# STM32G431CBU6.net
KiCad netlist of a schematic drawn in Altium Designer
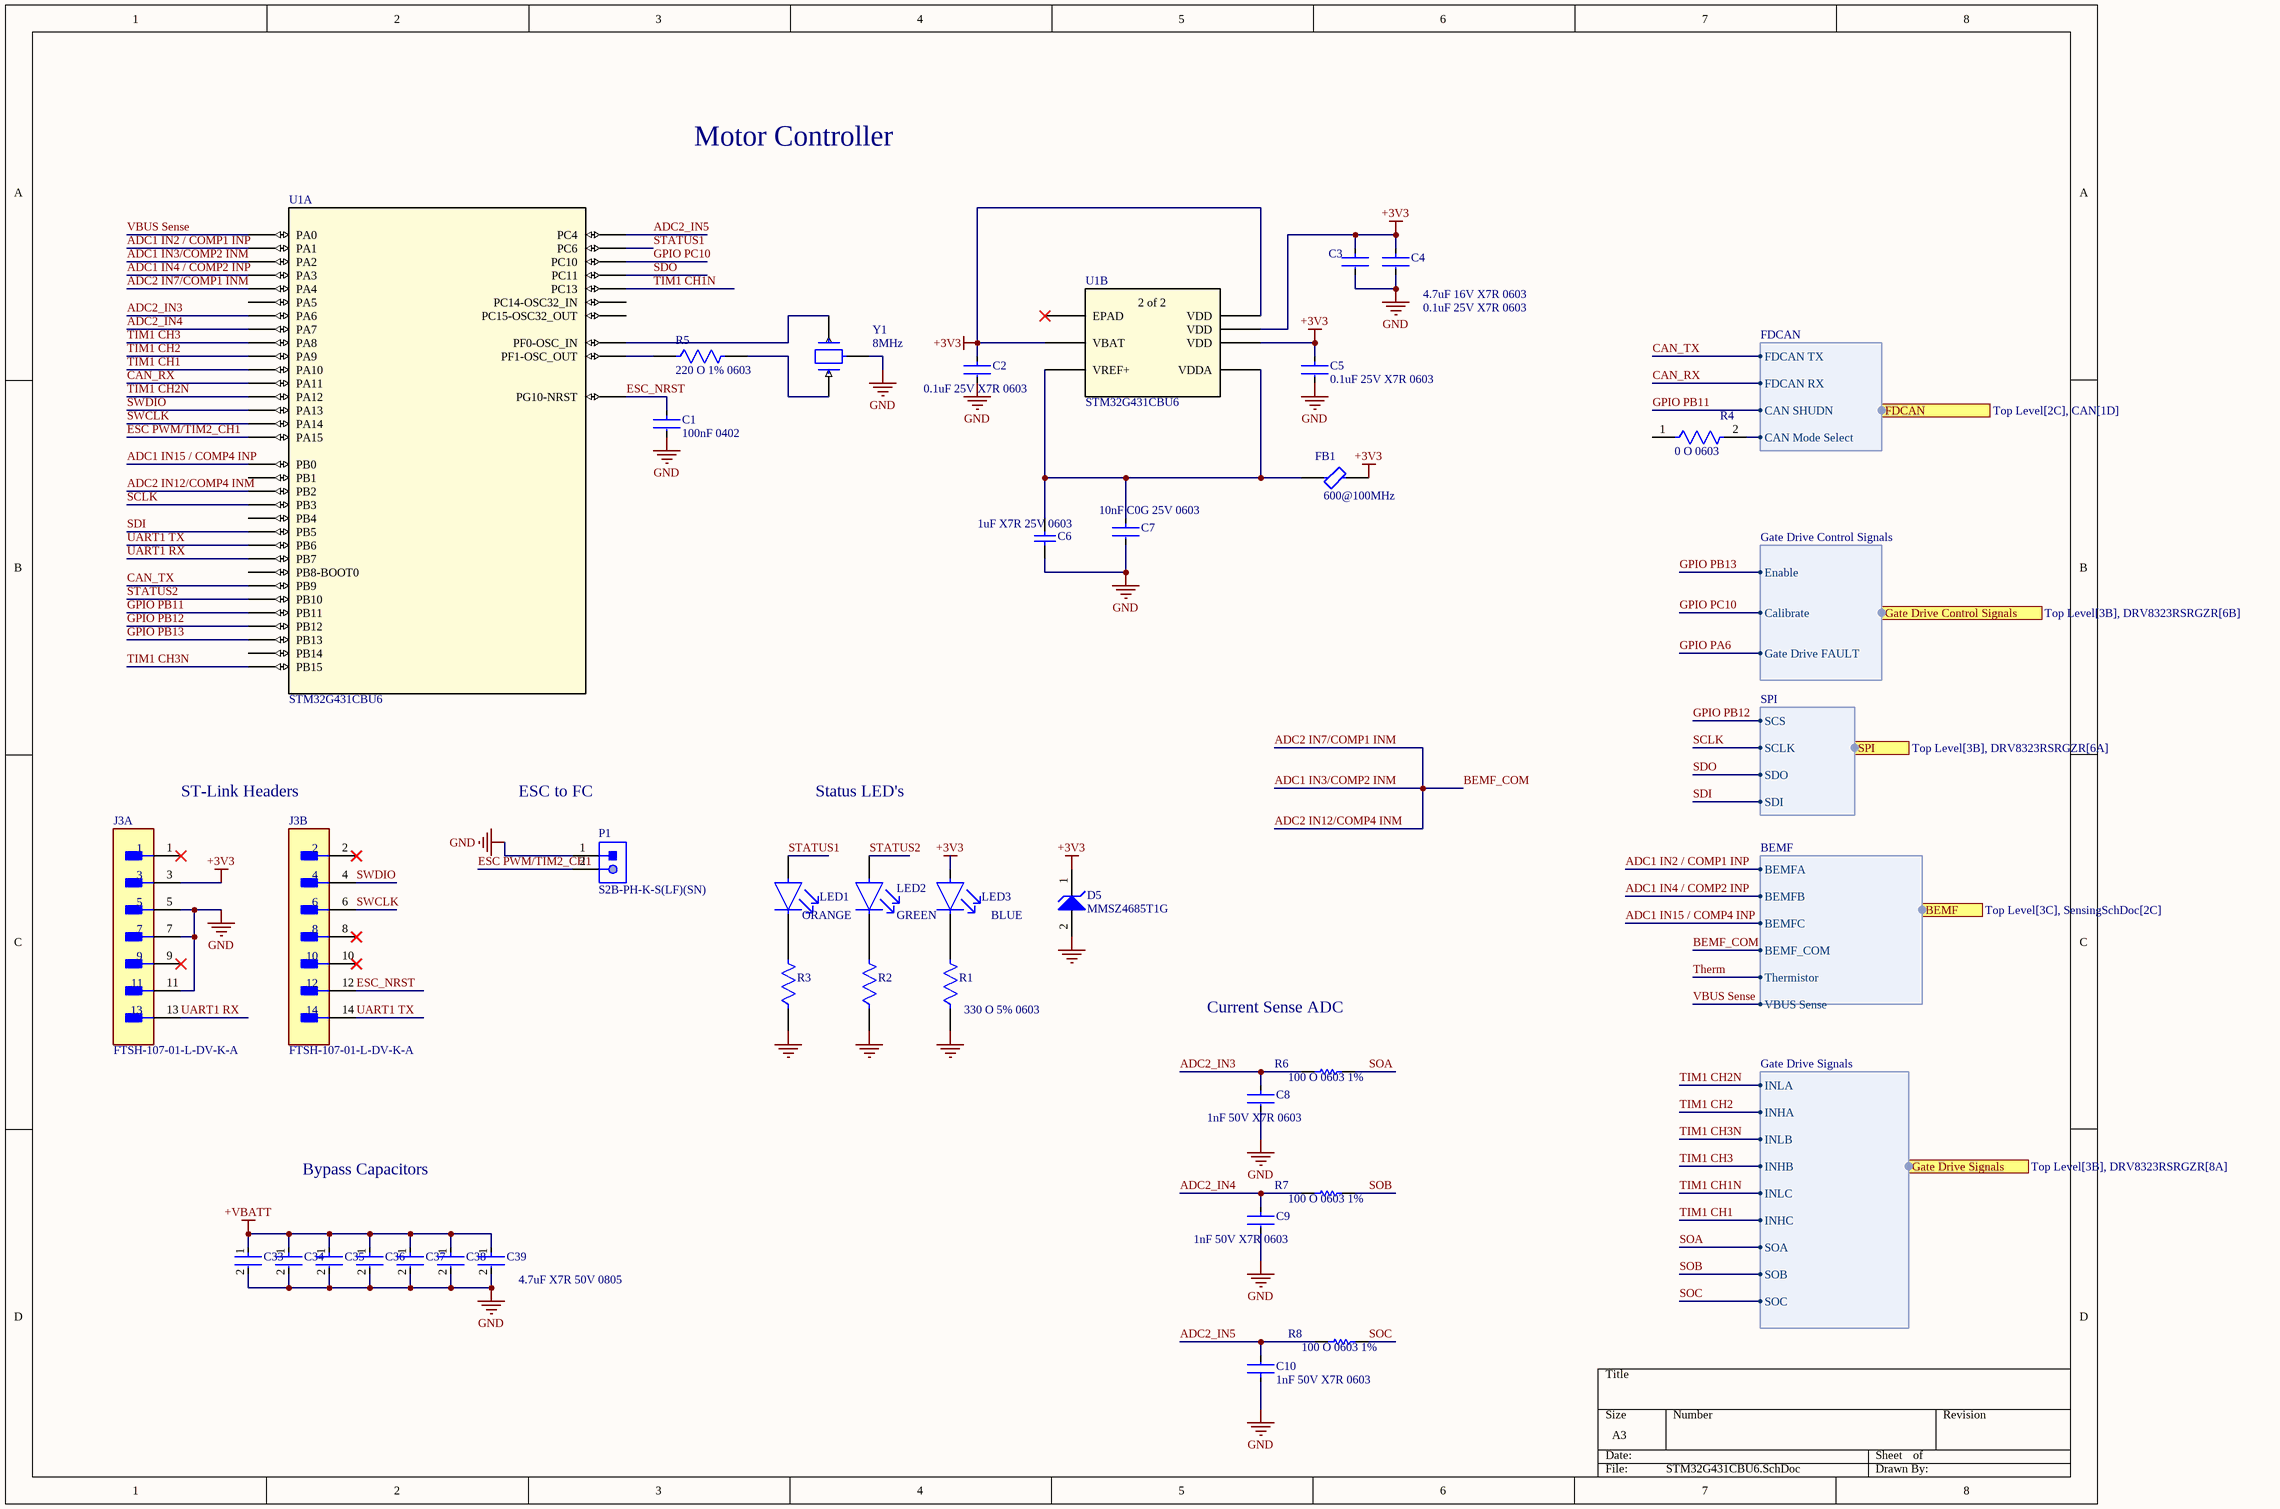
[diagram p0: STM32G431CBU6.SchDoc]

(export (version "E")
  (design (tool "Eeschema 10.0.6"))
  (components
    (comp (ref "C1")
      (value "100nF 0402")
      (footprint "FP-GRM155-0_05-MFG")
      (description "Chip Multilayer Ceramic Capacitors for General Purpose, 0402, 0.10uF, X7R, 15%, 20%, 25V")
      (libsource (lib "Altium Content Vault") (part "02cd4be3c70576c341d710602a673aa"))
    )
    (comp (ref "C2")
      (value "0.1uF 25V X7R 0603")
      (footprint "FP-C0603C-CF-MFG")
      (description "CAP CER 0.1UF 25V X7R 0603")
      (fields (field (name "TOLERANCE") "0.1") (field (name "MANUFACTURER PART NUMBER") "C0603C104K3RACAUTO"))
      (libsource (lib "") (part "b4654b650e69147ec39a6b967a45e02_1"))
    )
    (comp (ref "C3")
      (value "4.7uF 16V X7R 0603")
      (footprint "FP-GRM188-0_2-IPC_A")
      (description "Chip Multilayer Ceramic Capacitors for General Purpose, 0603, 4.7uF, X7R, 15%, 10%, 16V")
      (libsource (lib "Altium Content Vault") (part "11868f565c42a9108669ba33697ecf6"))
    )
    (comp (ref "C4")
      (value "0.1uF 25V X7R 0603")
      (footprint "FP-C0603C-CF-MFG")
      (description "CAP CER 0.1UF 25V X7R 0603")
      (fields (field (name "TOLERANCE") "0.1") (field (name "MANUFACTURER PART NUMBER") "C0603C104K3RACAUTO"))
      (libsource (lib "") (part "b4654b650e69147ec39a6b967a45e02_1"))
    )
    (comp (ref "C5")
      (value "0.1uF 25V X7R 0603")
      (footprint "FP-C0603C-CF-MFG")
      (description "CAP CER 0.1UF 25V X7R 0603")
      (fields (field (name "TOLERANCE") "0.1") (field (name "MANUFACTURER PART NUMBER") "C0603C104K3RACAUTO"))
      (libsource (lib "") (part "b4654b650e69147ec39a6b967a45e02_1"))
    )
    (comp (ref "C6")
      (value "1uF X7R 25V 0603")
      (footprint "CAPC1608X95X35NL15T15")
      (fields (field (name "PART NUMBER") "C0603C105M3RACTU") (field (name "MANUFACTURER") "Kemet"))
      (libsource (lib "Altium Content Vault") (part "CAP"))
    )
    (comp (ref "C7")
      (value "10nF C0G 25V 0603")
      (footprint "FP-C0603C-CF-MFG")
      (description "C0603 10,000 pF C0G 30ppm/°C 5.00% 25 V")
      (fields
        (field (name "OCTOPART") "https://octopart.com/c0603c103j3gacauto-kemet-75532652")
        (field (name "MANUFACTURER") "KEMET")
      )
      (libsource (lib "") (part "b4654b650e69147ec39a6b967a45e02_1"))
    )
    (comp (ref "C8")
      (value "1nF 50V X7R 0603")
      (footprint "FP-C0603C-CF-MFG")
      (description "CAP CER 1000PF 50V X7R 0603")
      (fields (field (name "TOLERANCE") "0.1") (field (name "MANUFACTURER PART NUMBER") "C0603C102K5RACAUTO"))
      (libsource (lib "") (part "b4654b650e69147ec39a6b967a45e02_1"))
    )
    (comp (ref "C9")
      (value "1nF 50V X7R 0603")
      (footprint "FP-C0603C-CF-MFG")
      (description "CAP CER 1000PF 50V X7R 0603")
      (fields (field (name "TOLERANCE") "0.1") (field (name "MANUFACTURER PART NUMBER") "C0603C102K5RACAUTO"))
      (libsource (lib "") (part "b4654b650e69147ec39a6b967a45e02_1"))
    )
    (comp (ref "C10")
      (value "1nF 50V X7R 0603")
      (footprint "FP-C0603C-CF-MFG")
      (description "CAP CER 1000PF 50V X7R 0603")
      (fields (field (name "TOLERANCE") "0.1") (field (name "MANUFACTURER PART NUMBER") "C0603C102K5RACAUTO"))
      (libsource (lib "") (part "b4654b650e69147ec39a6b967a45e02_1"))
    )
    (comp (ref "C33")
      (value "4.7uF X7R 50V 0805")
      (footprint "FP-GRM21B-0_2-e0_2_0_7-IPC_C")
      (description "Chip Multilayer Ceramic Capacitors for General Purpose, 0805, 4.7uF, X7R, 15%, 10%, 50V")
      (libsource (lib "Altium Content Vault") (part "b4654b650e69147ec39a6b967a45e02"))
    )
    (comp (ref "C34")
      (value "4.7uF X7R 50V 0805")
      (footprint "FP-GRM21B-0_2-e0_2_0_7-IPC_C")
      (description "Chip Multilayer Ceramic Capacitors for General Purpose, 0805, 4.7uF, X7R, 15%, 10%, 50V")
      (libsource (lib "Altium Content Vault") (part "b4654b650e69147ec39a6b967a45e02"))
    )
    (comp (ref "C35")
      (value "4.7uF X7R 50V 0805")
      (footprint "FP-GRM21B-0_2-e0_2_0_7-IPC_C")
      (description "Chip Multilayer Ceramic Capacitors for General Purpose, 0805, 4.7uF, X7R, 15%, 10%, 50V")
      (libsource (lib "Altium Content Vault") (part "b4654b650e69147ec39a6b967a45e02"))
    )
    (comp (ref "C36")
      (value "4.7uF X7R 50V 0805")
      (footprint "FP-GRM21B-0_2-e0_2_0_7-IPC_C")
      (description "Chip Multilayer Ceramic Capacitors for General Purpose, 0805, 4.7uF, X7R, 15%, 10%, 50V")
      (libsource (lib "Altium Content Vault") (part "b4654b650e69147ec39a6b967a45e02"))
    )
    (comp (ref "C37")
      (value "4.7uF X7R 50V 0805")
      (footprint "FP-GRM21B-0_2-e0_2_0_7-IPC_C")
      (description "Chip Multilayer Ceramic Capacitors for General Purpose, 0805, 4.7uF, X7R, 15%, 10%, 50V")
      (libsource (lib "Altium Content Vault") (part "b4654b650e69147ec39a6b967a45e02"))
    )
    (comp (ref "C38")
      (value "4.7uF X7R 50V 0805")
      (footprint "FP-GRM21B-0_2-e0_2_0_7-IPC_C")
      (description "Chip Multilayer Ceramic Capacitors for General Purpose, 0805, 4.7uF, X7R, 15%, 10%, 50V")
      (libsource (lib "Altium Content Vault") (part "b4654b650e69147ec39a6b967a45e02"))
    )
    (comp (ref "C39")
      (value "4.7uF X7R 50V 0805")
      (footprint "FP-GRM21B-0_2-e0_2_0_7-IPC_C")
      (description "Chip Multilayer Ceramic Capacitors for General Purpose, 0805, 4.7uF, X7R, 15%, 10%, 50V")
      (libsource (lib "Altium Content Vault") (part "b4654b650e69147ec39a6b967a45e02"))
    )
    (comp (ref "D5")
      (value "MMSZ4685T1G")
      (footprint "ONSC-SOD-123-2-425-04_V")
      (description "Zener Voltage Regulator, 500 mW, 2-Pin SOD-123, Pb-Free, Tape and Reel")
      (fields (field (name "MANUFACTURER") "On Semiconductor"))
      (libsource (lib "Altium Content Vault") (part "ONSC-K1A2-2"))
    )
    (comp (ref "FB1")
      (value "600@100MHz")
      (footprint "FP-MPZ1608-0_8-MFG")
      (description "Power line Ferrite Bead 600Ω @ 100MHz 1A DCR 0.15Ω SMD 0603")
      (fields (field (name "TOLERANCE") "25%"))
      (libsource (lib "Altium Content Vault") (part "5f30dd21d616792df468990f7003faa"))
    )
    (comp (ref "J3")
      (value "FTSH-107-01-L-DV-K-A")
      (footprint "FP-FTSH-107-01-L-DV-K-A-MFG")
      (description "CONN HEADER SMD 14POS 1.27MM")
      (libsource (lib "Altium Content Vault") (part "45cc164b9edde9e1ad516d884ad4e1e"))
    )
    (comp (ref "LED1")
      (value "ORANGE")
      (footprint "FP-6_541-5092_01-4-MFG")
      (description "VLMO1300-GS08 LED Uni-Color Soft Orange 611nm 2-Pin Chip 0603(1608Metric) T/R")
      (libsource (lib "Altium Content Vault") (part "8706943c75ba83719d021d2fdc84c58"))
    )
    (comp (ref "LED2")
      (value "GREEN")
      (footprint "FP-LTST-C193KGKT-5A-MFG")
      (description "LED GREEN CLEAR CHIP SMD")
      (libsource (lib "Altium Content Vault") (part "8706943c75ba83719d021d2fdc84c58"))
    )
    (comp (ref "LED3")
      (value "BLUE")
      (footprint "FP-APT1608QBC-D-MFG")
      (description "LED BLUE CLEAR CHIP SMD")
      (libsource (lib "Altium Content Vault") (part "8706943c75ba83719d021d2fdc84c58"))
    )
    (comp (ref "P1")
      (value "S2B-PH-K-S(LF)(SN)")
      (footprint "JST-S2B-PH-K-S_V")
      (fields (field (name "TOLERANCE") "20%"))
      (libsource (lib "Altium Content Vault") (part "CN-1P-M-R2"))
    )
    (comp (ref "R1")
      (value "330 O 5% 0603")
      (footprint "FP-AC0603-IPC_C")
      (description "RES 330Ω 5.00% 0.1W 0603")
      (fields (field (name "TOLERANCE") "5%"))
      (libsource (lib "") (part "1029c3af85768c4190bb7ad29bc67b5_1"))
    )
    (comp (ref "R2")
      (value "AC0603JR-07330RL")
      (footprint "FP-AC0603-IPC_C")
      (description "RES 330Ω 5.00% 0.1W 0603")
      (fields (field (name "TOLERANCE") "5%"))
      (libsource (lib "") (part "1029c3af85768c4190bb7ad29bc67b5_1"))
    )
    (comp (ref "R3")
      (value "AC0603JR-07330RL")
      (footprint "FP-AC0603-IPC_C")
      (description "RES 330Ω 5.00% 0.1W 0603")
      (fields (field (name "TOLERANCE") "5%"))
      (libsource (lib "") (part "1029c3af85768c4190bb7ad29bc67b5_1"))
    )
    (comp (ref "R4")
      (value "0 O 0603")
      (footprint "FP-MCT0603-IPC_C")
      (description "RES SMD 100 OHM 1% 1/8W 0603")
      (libsource (lib "Altium Content Vault") (part "1029c3af85768c4190bb7ad29bc67b5"))
    )
    (comp (ref "R5")
      (value "220 O 1% 0603")
      (footprint "FP-AC0603-IPC_A")
      (description "RES 220Ω 1.00% 0.1W 0603")
      (fields (field (name "TOLERANCE") "1%"))
      (libsource (lib "") (part "1029c3af85768c4190bb7ad29bc67b5_1"))
    )
    (comp (ref "R6")
      (value "100 O 0603 1%")
      (footprint "RESC1608X55X25ML10T15")
      (fields (field (name "PART NUMBER") "RC0603FR-10100RL") (field (name "MANUFACTURER") "Yageo"))
      (libsource (lib "Altium Content Vault") (part "RES"))
    )
    (comp (ref "R7")
      (value "100 O 0603 1%")
      (footprint "RESC1608X55X25ML10T15")
      (fields (field (name "PART NUMBER") "RC0603FR-10100RL") (field (name "MANUFACTURER") "Yageo"))
      (libsource (lib "Altium Content Vault") (part "RES"))
    )
    (comp (ref "R8")
      (value "100 O 0603 1%")
      (footprint "RESC1608X55X25ML10T15")
      (fields (field (name "PART NUMBER") "RC0603FR-10100RL") (field (name "MANUFACTURER") "Yageo"))
      (libsource (lib "Altium Content Vault") (part "RES"))
    )
    (comp (ref "U1")
      (value "STM32G431CBU6")
      (footprint "UFQFPN-48_7X7X0P55MM")
      (fields (field (name "COPYRIGHT") "Copyright (C) 2025 Ultra Librarian. All rights reserved."))
      (libsource (lib "STM32G431CBU6") (part "STM32G431CBU6"))
    )
    (comp (ref "Y1")
      (value "8MHz")
      (footprint "FP-CSTNE8M00GH5C000R0-MFG")
      (description "CERAMIC RES 8.0000MHZ 33PF SMD")
      (libsource (lib "Altium Content Vault") (part "7d37667f5012bb31280c8009ddd0b1c"))
    )
  )
  (nets
    (net (code "8") (name "+3V3") (class "Default")
      (node (ref "C2") (pin "1") (pinfunction "1_1") (pintype "passive"))
      (node (ref "C3") (pin "1") (pinfunction "1_1") (pintype "passive"))
      (node (ref "C4") (pin "1") (pinfunction "1_1") (pintype "passive"))
      (node (ref "C5") (pin "1") (pinfunction "1_1") (pintype "passive"))
      (node (ref "D5") (pin "1") (pinfunction "K_1") (pintype "passive"))
      (node (ref "FB1") (pin "2") (pinfunction "2_2") (pintype "passive"))
      (node (ref "J3") (pin "3") (pinfunction "3_3") (pintype "passive"))
      (node (ref "LED3") (pin "2") (pinfunction "A_2") (pintype "passive"))
      (node (ref "U1") (pin "1") (pinfunction "VBAT_1") (pintype "power_in"))
      (node (ref "U1") (pin "23") (pinfunction "VDD_23") (pintype "power_in"))
      (node (ref "U1") (pin "35") (pinfunction "VDD_35") (pintype "power_in"))
      (node (ref "U1") (pin "48") (pinfunction "VDD_48") (pintype "power_in"))
    )
    (net (code "9") (name "+VBATT") (class "Default")
      (node (ref "C33") (pin "1") (pinfunction "1_1") (pintype "passive"))
      (node (ref "C34") (pin "1") (pinfunction "1_1") (pintype "passive"))
      (node (ref "C35") (pin "1") (pinfunction "1_1") (pintype "passive"))
      (node (ref "C36") (pin "1") (pinfunction "1_1") (pintype "passive"))
      (node (ref "C37") (pin "1") (pinfunction "1_1") (pintype "passive"))
      (node (ref "C38") (pin "1") (pinfunction "1_1") (pintype "passive"))
      (node (ref "C39") (pin "1") (pinfunction "1_1") (pintype "passive"))
    )
    (net (code "10") (name "/ADC1 IN2 {slash} COMP1 INP") (class "Default")
      (node (ref "U1") (pin "9") (pinfunction "PA1_9") (pintype "bidirectional"))
    )
    (net (code "11") (name "/ADC1 IN3{slash}COMP2 INM") (class "Default")
      (node (ref "U1") (pin "10") (pinfunction "PA2_10") (pintype "bidirectional"))
      (node (ref "U1") (pin "12") (pinfunction "PA4_12") (pintype "bidirectional"))
      (node (ref "U1") (pin "19") (pinfunction "PB2_19") (pintype "bidirectional"))
    )
    (net (code "12") (name "/ADC1 IN4 {slash} COMP2 INP") (class "Default")
      (node (ref "U1") (pin "11") (pinfunction "PA3_11") (pintype "bidirectional"))
    )
    (net (code "13") (name "/ADC1 IN15 {slash} COMP4 INP") (class "Default")
      (node (ref "U1") (pin "17") (pinfunction "PB0_17") (pintype "bidirectional"))
    )
    (net (code "14") (name "/ADC2_IN3") (class "Default")
      (node (ref "C8") (pin "1") (pinfunction "1_1") (pintype "passive"))
      (node (ref "R6") (pin "1") (pinfunction "1_1") (pintype "passive"))
      (node (ref "U1") (pin "14") (pinfunction "PA6_14") (pintype "bidirectional"))
    )
    (net (code "15") (name "/ADC2_IN4") (class "Default")
      (node (ref "C9") (pin "1") (pinfunction "1_1") (pintype "passive"))
      (node (ref "R7") (pin "1") (pinfunction "1_1") (pintype "passive"))
      (node (ref "U1") (pin "15") (pinfunction "PA7_15") (pintype "bidirectional"))
    )
    (net (code "16") (name "/ADC2_IN5") (class "Default")
      (node (ref "C10") (pin "2") (pinfunction "2_2") (pintype "passive"))
      (node (ref "R8") (pin "1") (pinfunction "1_1") (pintype "passive"))
      (node (ref "U1") (pin "16") (pinfunction "PC4_16") (pintype "bidirectional"))
    )
    (net (code "17") (name "/CAN Mode Select") (class "Default")
      (node (ref "R4") (pin "2") (pinfunction "2_2") (pintype "passive"))
    )
    (net (code "18") (name "/CAN_RX") (class "Default")
      (node (ref "U1") (pin "33") (pinfunction "PA11_33") (pintype "bidirectional"))
    )
    (net (code "19") (name "/CAN_TX") (class "Default")
      (node (ref "U1") (pin "47") (pinfunction "PB9_47") (pintype "bidirectional"))
    )
    (net (code "20") (name "/ESC PWM{slash}TIM2_CH1") (class "Default")
      (node (ref "P1") (pin "2") (pinfunction "2_2") (pintype "passive"))
      (node (ref "U1") (pin "38") (pinfunction "PA15_38") (pintype "bidirectional"))
    )
    (net (code "21") (name "/ESC_NRST") (class "Default")
      (node (ref "C1") (pin "1") (pinfunction "1_1") (pintype "passive"))
      (node (ref "J3") (pin "12") (pinfunction "12_12") (pintype "passive"))
      (node (ref "U1") (pin "7") (pinfunction "PG10-NRST_7") (pintype "bidirectional"))
    )
    (net (code "23") (name "/GPIO PB11") (class "Default")
      (node (ref "U1") (pin "24") (pinfunction "PB11_24") (pintype "bidirectional"))
    )
    (net (code "24") (name "/GPIO PB12") (class "Default")
      (node (ref "U1") (pin "25") (pinfunction "PB12_25") (pintype "bidirectional"))
    )
    (net (code "25") (name "/GPIO PB13") (class "Default")
      (node (ref "U1") (pin "26") (pinfunction "PB13_26") (pintype "bidirectional"))
    )
    (net (code "26") (name "/GPIO PC10") (class "Default")
      (node (ref "U1") (pin "39") (pinfunction "PC10_39") (pintype "bidirectional"))
    )
    (net (code "27") (name "/SCLK") (class "Default")
      (node (ref "U1") (pin "41") (pinfunction "PB3_41") (pintype "bidirectional"))
    )
    (net (code "28") (name "/SDI") (class "Default")
      (node (ref "U1") (pin "43") (pinfunction "PB5_43") (pintype "bidirectional"))
    )
    (net (code "29") (name "/SDO") (class "Default")
      (node (ref "U1") (pin "40") (pinfunction "PC11_40") (pintype "bidirectional"))
    )
    (net (code "30") (name "/SOA") (class "Default")
      (node (ref "R6") (pin "2") (pinfunction "2_2") (pintype "passive"))
    )
    (net (code "31") (name "/SOB") (class "Default")
      (node (ref "R7") (pin "2") (pinfunction "2_2") (pintype "passive"))
    )
    (net (code "32") (name "/SOC") (class "Default")
      (node (ref "R8") (pin "2") (pinfunction "2_2") (pintype "passive"))
    )
    (net (code "33") (name "/STATUS1") (class "Default")
      (node (ref "LED1") (pin "2") (pinfunction "A_2") (pintype "passive"))
      (node (ref "U1") (pin "29") (pinfunction "PC6_29") (pintype "bidirectional"))
    )
    (net (code "34") (name "/STATUS2") (class "Default")
      (node (ref "LED2") (pin "2") (pinfunction "A_2") (pintype "passive"))
      (node (ref "U1") (pin "22") (pinfunction "PB10_22") (pintype "bidirectional"))
    )
    (net (code "35") (name "/SWCLK") (class "Default")
      (node (ref "J3") (pin "6") (pinfunction "6_6") (pintype "passive"))
      (node (ref "U1") (pin "37") (pinfunction "PA14_37") (pintype "bidirectional"))
    )
    (net (code "36") (name "/SWDIO") (class "Default")
      (node (ref "J3") (pin "4") (pinfunction "4_4") (pintype "passive"))
      (node (ref "U1") (pin "36") (pinfunction "PA13_36") (pintype "bidirectional"))
    )
    (net (code "37") (name "/TIM1 CH1") (class "Default")
      (node (ref "U1") (pin "32") (pinfunction "PA10_32") (pintype "bidirectional"))
    )
    (net (code "38") (name "/TIM1 CH1N") (class "Default")
      (node (ref "U1") (pin "2") (pinfunction "PC13_2") (pintype "bidirectional"))
    )
    (net (code "39") (name "/TIM1 CH2") (class "Default")
      (node (ref "U1") (pin "31") (pinfunction "PA9_31") (pintype "bidirectional"))
    )
    (net (code "40") (name "/TIM1 CH2N") (class "Default")
      (node (ref "U1") (pin "34") (pinfunction "PA12_34") (pintype "bidirectional"))
    )
    (net (code "41") (name "/TIM1 CH3") (class "Default")
      (node (ref "U1") (pin "30") (pinfunction "PA8_30") (pintype "bidirectional"))
    )
    (net (code "42") (name "/TIM1 CH3N") (class "Default")
      (node (ref "U1") (pin "28") (pinfunction "PB15_28") (pintype "bidirectional"))
    )
    (net (code "44") (name "/UART1 RX") (class "Default")
      (node (ref "J3") (pin "13") (pinfunction "13_13") (pintype "passive"))
      (node (ref "U1") (pin "45") (pinfunction "PB7_45") (pintype "bidirectional"))
    )
    (net (code "45") (name "/UART1 TX") (class "Default")
      (node (ref "J3") (pin "14") (pinfunction "14_14") (pintype "passive"))
      (node (ref "U1") (pin "44") (pinfunction "PB6_44") (pintype "bidirectional"))
    )
    (net (code "46") (name "/VBUS Sense") (class "Default")
      (node (ref "U1") (pin "8") (pinfunction "PA0_8") (pintype "bidirectional"))
    )
    (net (code "52") (name "GND") (class "Default")
      (node (ref "C1") (pin "2") (pinfunction "2_2") (pintype "passive"))
      (node (ref "C10") (pin "1") (pinfunction "1_1") (pintype "passive"))
      (node (ref "C2") (pin "2") (pinfunction "2_2") (pintype "passive"))
      (node (ref "C3") (pin "2") (pinfunction "2_2") (pintype "passive"))
      (node (ref "C33") (pin "2") (pinfunction "2_2") (pintype "passive"))
      (node (ref "C34") (pin "2") (pinfunction "2_2") (pintype "passive"))
      (node (ref "C35") (pin "2") (pinfunction "2_2") (pintype "passive"))
      (node (ref "C36") (pin "2") (pinfunction "2_2") (pintype "passive"))
      (node (ref "C37") (pin "2") (pinfunction "2_2") (pintype "passive"))
      (node (ref "C38") (pin "2") (pinfunction "2_2") (pintype "passive"))
      (node (ref "C39") (pin "2") (pinfunction "2_2") (pintype "passive"))
      (node (ref "C4") (pin "2") (pinfunction "2_2") (pintype "passive"))
      (node (ref "C5") (pin "2") (pinfunction "2_2") (pintype "passive"))
      (node (ref "C6") (pin "1") (pinfunction "1_1") (pintype "passive"))
      (node (ref "C7") (pin "2") (pinfunction "2_2") (pintype "passive"))
      (node (ref "C8") (pin "2") (pinfunction "2_2") (pintype "passive"))
      (node (ref "C9") (pin "2") (pinfunction "2_2") (pintype "passive"))
      (node (ref "D5") (pin "2") (pinfunction "A_2") (pintype "passive"))
      (node (ref "J3") (pin "11") (pinfunction "11_11") (pintype "passive"))
      (node (ref "J3") (pin "5") (pinfunction "5_5") (pintype "passive"))
      (node (ref "J3") (pin "7") (pinfunction "7_7") (pintype "passive"))
      (node (ref "P1") (pin "1") (pinfunction "1_1") (pintype "passive"))
      (node (ref "R1") (pin "1") (pinfunction "1_1") (pintype "passive"))
      (node (ref "R2") (pin "1") (pinfunction "1_1") (pintype "passive"))
      (node (ref "R3") (pin "1") (pinfunction "1_1") (pintype "passive"))
      (node (ref "Y1") (pin "2") (pinfunction "GND_2") (pintype "power_in"))
    )
    (net (code "53") (name "Net-(LED1-C)") (class "Default")
      (node (ref "LED1") (pin "1") (pinfunction "C_1") (pintype "passive"))
      (node (ref "R3") (pin "2") (pinfunction "2_2") (pintype "passive"))
    )
    (net (code "54") (name "Net-(LED2-C)") (class "Default")
      (node (ref "LED2") (pin "1") (pinfunction "C_1") (pintype "passive"))
      (node (ref "R2") (pin "2") (pinfunction "2_2") (pintype "passive"))
    )
    (net (code "55") (name "Net-(LED3-C)") (class "Default")
      (node (ref "LED3") (pin "1") (pinfunction "C_1") (pintype "passive"))
      (node (ref "R1") (pin "2") (pinfunction "2_2") (pintype "passive"))
    )
    (net (code "56") (name "Net-(U1A-PF0-OSC_IN)") (class "Default")
      (node (ref "U1") (pin "5") (pinfunction "PF0-OSC_IN_5") (pintype "bidirectional"))
      (node (ref "Y1") (pin "3") (pinfunction "Output_3") (pintype "output"))
    )
    (net (code "57") (name "Net-(U1A-PF1-OSC_OUT)") (class "Default")
      (node (ref "R5") (pin "1") (pinfunction "1_1") (pintype "passive"))
      (node (ref "U1") (pin "6") (pinfunction "PF1-OSC_OUT_6") (pintype "bidirectional"))
    )
    (net (code "58") (name "Net-(U1B-VDDA)") (class "Default")
      (node (ref "C6") (pin "2") (pinfunction "2_2") (pintype "passive"))
      (node (ref "C7") (pin "1") (pinfunction "1_1") (pintype "passive"))
      (node (ref "FB1") (pin "1") (pinfunction "1_1") (pintype "passive"))
      (node (ref "U1") (pin "20") (pinfunction "VREF+_20") (pintype "power_in"))
      (node (ref "U1") (pin "21") (pinfunction "VDDA_21") (pintype "power_in"))
    )
    (net (code "59") (name "Net-(Y1-Input)") (class "Default")
      (node (ref "R5") (pin "2") (pinfunction "2_2") (pintype "passive"))
      (node (ref "Y1") (pin "1") (pinfunction "Input_1") (pintype "input"))
    )
    (net (code "60") (name "unconnected-(J3-Pad1)") (class "Default")
      (node (ref "J3") (pin "1") (pinfunction "1_1") (pintype "passive+no_connect"))
    )
    (net (code "61") (name "unconnected-(J3-Pad2)") (class "Default")
      (node (ref "J3") (pin "2") (pinfunction "2_2") (pintype "passive+no_connect"))
    )
    (net (code "62") (name "unconnected-(J3-Pad8)") (class "Default")
      (node (ref "J3") (pin "8") (pinfunction "8_8") (pintype "passive+no_connect"))
    )
    (net (code "63") (name "unconnected-(J3-Pad9)") (class "Default")
      (node (ref "J3") (pin "9") (pinfunction "9_9") (pintype "passive+no_connect"))
    )
    (net (code "64") (name "unconnected-(J3-Pad10)") (class "Default")
      (node (ref "J3") (pin "10") (pinfunction "10_10") (pintype "passive+no_connect"))
    )
    (net (code "65") (name "unconnected-(R4-Pad1)") (class "Default")
      (node (ref "R4") (pin "1") (pinfunction "1_1") (pintype "passive"))
    )
    (net (code "66") (name "unconnected-(U1A-PA5-Pad13)") (class "Default")
      (node (ref "U1") (pin "13") (pinfunction "PA5_13") (pintype "bidirectional"))
    )
    (net (code "67") (name "unconnected-(U1A-PB1-Pad18)") (class "Default")
      (node (ref "U1") (pin "18") (pinfunction "PB1_18") (pintype "bidirectional"))
    )
    (net (code "68") (name "unconnected-(U1A-PB4-Pad42)") (class "Default")
      (node (ref "U1") (pin "42") (pinfunction "PB4_42") (pintype "bidirectional"))
    )
    (net (code "69") (name "unconnected-(U1A-PB8-BOOT0-Pad46)") (class "Default")
      (node (ref "U1") (pin "46") (pinfunction "PB8-BOOT0_46") (pintype "bidirectional"))
    )
    (net (code "70") (name "unconnected-(U1A-PB14-Pad27)") (class "Default")
      (node (ref "U1") (pin "27") (pinfunction "PB14_27") (pintype "bidirectional"))
    )
    (net (code "71") (name "unconnected-(U1A-PC14-OSC32_IN-Pad3)") (class "Default")
      (node (ref "U1") (pin "3") (pinfunction "PC14-OSC32_IN_3") (pintype "bidirectional"))
    )
    (net (code "72") (name "unconnected-(U1A-PC15-OSC32_OUT-Pad4)") (class "Default")
      (node (ref "U1") (pin "4") (pinfunction "PC15-OSC32_OUT_4") (pintype "bidirectional"))
    )
    (net (code "73") (name "unconnected-(U1B-EPAD-Pad49)") (class "Default")
      (node (ref "U1") (pin "49") (pinfunction "EPAD_49") (pintype "passive+no_connect"))
    )
  )
)
